# USBBracket.net
KiCad netlist of a schematic drawn in Altium Designer
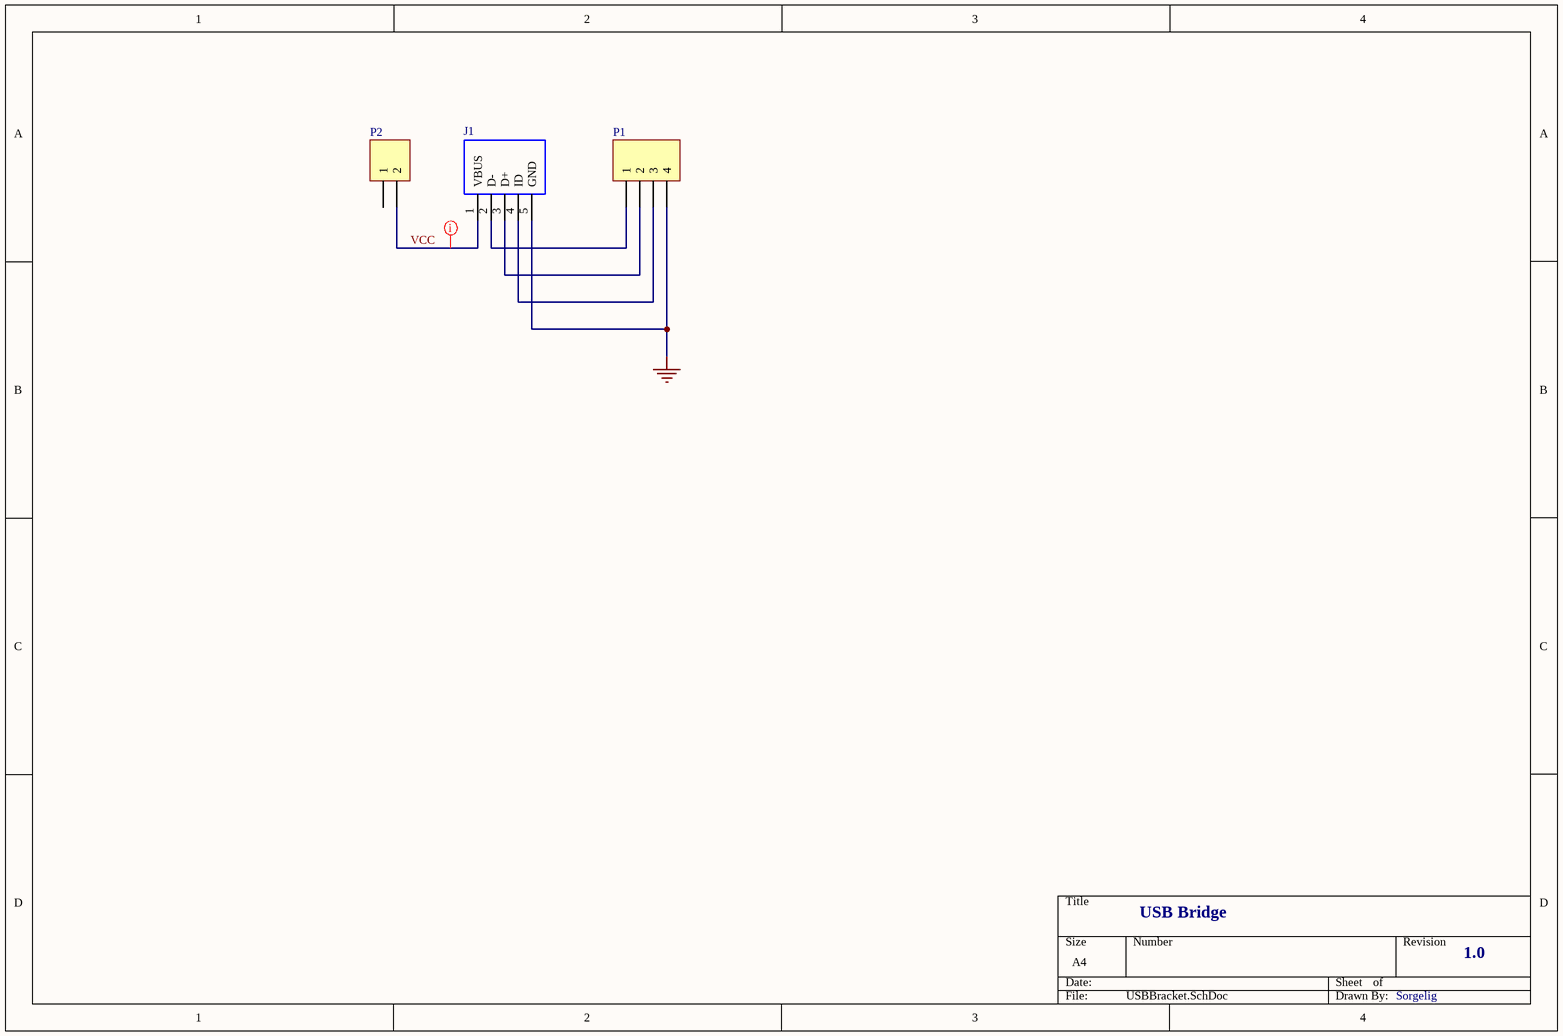
[diagram p0: USBBracket.SchDoc]

(export (version "E")
  (design (tool "Eeschema 10.0.6"))
  (components
    (comp (ref "J1")
      (value "MicroUSB-L")
      (footprint "MicroUSB-L")
      (fields
        (field (name "MANUFACTURER_PART_NUMBER") "47346-0001")
        (field (name "MOUSER PART NUMBER") "538-47346-0001")
        (field (name "RS PART NUMBER") "7025475P")
      )
      (libsource (lib "lib") (part "MicroUSB-L"))
    )
    (comp (ref "P1")
      (value "Header 4")
      (footprint "HDR1X4")
      (description "Header, 4-Pin")
      (fields (field (name "PUBLISHER") "Altium Limited"))
      (libsource (lib "Miscellaneous Connectors") (part "Header 4"))
    )
    (comp (ref "P2")
      (value "Header 2")
      (footprint "HDR1X2")
      (description "Header, 2-Pin")
      (fields (field (name "PUBLISHER") "Altium Limited"))
      (libsource (lib "Miscellaneous Connectors") (part "Header 2"))
    )
  )
  (nets
    (net (code "1") (name "/VCC") (class "Default")
      (node (ref "J1") (pin "1") (pinfunction "VBUS_1") (pintype "passive"))
      (node (ref "P2") (pin "2") (pinfunction "2_2") (pintype "passive"))
    )
    (net (code "2") (name "GND") (class "Default")
      (node (ref "J1") (pin "5") (pinfunction "GND_5") (pintype "passive"))
      (node (ref "P1") (pin "4") (pinfunction "4_4") (pintype "passive"))
    )
    (net (code "3") (name "Net-(J1-D+)") (class "Default")
      (node (ref "J1") (pin "3") (pinfunction "D+_3") (pintype "passive"))
      (node (ref "P1") (pin "2") (pinfunction "2_2") (pintype "passive"))
    )
    (net (code "4") (name "Net-(J1-D-)") (class "Default")
      (node (ref "J1") (pin "2") (pinfunction "D-_2") (pintype "passive"))
      (node (ref "P1") (pin "1") (pinfunction "1_1") (pintype "passive"))
    )
    (net (code "5") (name "Net-(J1-ID)") (class "Default")
      (node (ref "J1") (pin "4") (pinfunction "ID_4") (pintype "passive"))
      (node (ref "P1") (pin "3") (pinfunction "3_3") (pintype "passive"))
    )
    (net (code "6") (name "unconnected-(P2-Pad1)") (class "Default")
      (node (ref "P2") (pin "1") (pinfunction "1_1") (pintype "passive"))
    )
  )
)
